# atv_sheild1.net
KiCad netlist of a schematic drawn in EAGLE
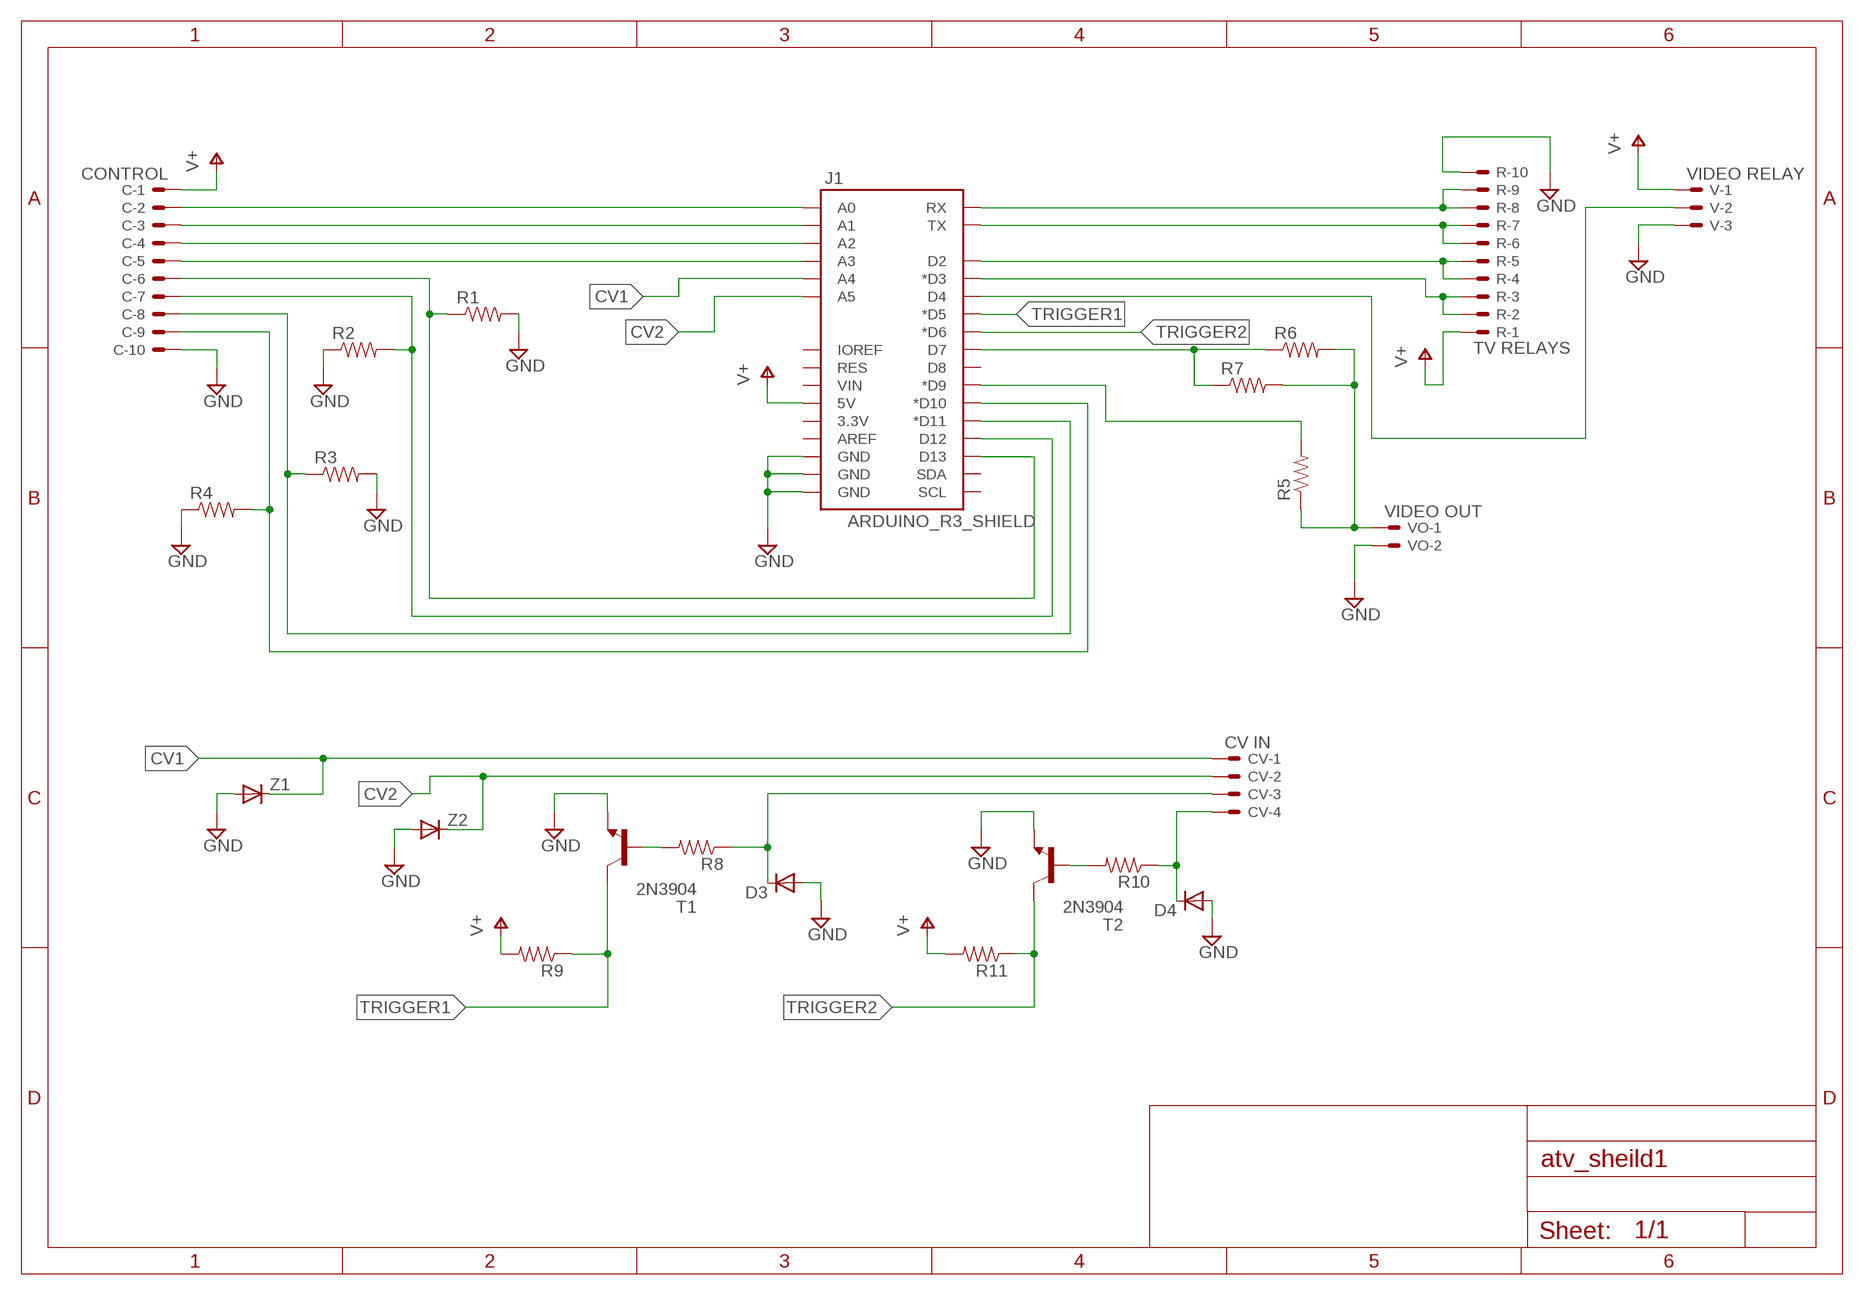
[diagram p0: schematic, sheet 1]

(export (version "E")
  (design (tool "Eeschema 10.0.6"))
  (components
    (comp (ref "C")
      (value "CONTROL")
      (footprint "eagle-import:22-23-2101")
      (fields (field (name "MF") "MOLEX") (field (name "MPN") "22-23-2101"))
      (libsource (lib "eagle-import") (part "22-23-2101"))
    )
    (comp (ref "CV")
      (value "CV IN")
      (footprint "eagle-import:22-23-2041")
      (fields (field (name "MF") "MOLEX") (field (name "MPN") "22-23-2041"))
      (libsource (lib "eagle-import") (part "22-23-2041"))
    )
    (comp (ref "D3")
      (value "SMALL_DIODEDO35-7")
      (footprint "eagle-import:DO35-7")
      (libsource (lib "eagle-import") (part "SMALL_DIODEDO35-7"))
    )
    (comp (ref "D4")
      (value "SMALL_DIODEDO35-7")
      (footprint "eagle-import:DO35-7")
      (libsource (lib "eagle-import") (part "SMALL_DIODEDO35-7"))
    )
    (comp (ref "J1")
      (value "ARDUINO_R3_SHIELD")
      (footprint "eagle-import:UNO_R3_SHIELD")
      (libsource (lib "eagle-import") (part "ARDUINO_R3_SHIELD"))
    )
    (comp (ref "R")
      (value "TV RELAYS")
      (footprint "eagle-import:22-23-2101")
      (fields (field (name "MF") "MOLEX") (field (name "MPN") "22-23-2101"))
      (libsource (lib "eagle-import") (part "22-23-2101"))
    )
    (comp (ref "R1")
      (value "RESISTORPTH-1/4W")
      (footprint "eagle-import:AXIAL-0.4")
      (libsource (lib "eagle-import") (part "RESISTORPTH-1/4W"))
    )
    (comp (ref "R2")
      (value "RESISTORPTH-1/4W")
      (footprint "eagle-import:AXIAL-0.4")
      (libsource (lib "eagle-import") (part "RESISTORPTH-1/4W"))
    )
    (comp (ref "R3")
      (value "RESISTORPTH-1/4W")
      (footprint "eagle-import:AXIAL-0.4")
      (libsource (lib "eagle-import") (part "RESISTORPTH-1/4W"))
    )
    (comp (ref "R4")
      (value "RESISTORPTH-1/4W")
      (footprint "eagle-import:AXIAL-0.4")
      (libsource (lib "eagle-import") (part "RESISTORPTH-1/4W"))
    )
    (comp (ref "R5")
      (value "RESISTORPTH-1/4W")
      (footprint "eagle-import:AXIAL-0.4")
      (libsource (lib "eagle-import") (part "RESISTORPTH-1/4W"))
    )
    (comp (ref "R6")
      (value "RESISTORPTH-1/4W")
      (footprint "eagle-import:AXIAL-0.4")
      (libsource (lib "eagle-import") (part "RESISTORPTH-1/4W"))
    )
    (comp (ref "R7")
      (value "RESISTORPTH-1/4W")
      (footprint "eagle-import:AXIAL-0.4")
      (libsource (lib "eagle-import") (part "RESISTORPTH-1/4W"))
    )
    (comp (ref "R8")
      (value "RESISTORPTH-1/4W")
      (footprint "eagle-import:AXIAL-0.4")
      (libsource (lib "eagle-import") (part "RESISTORPTH-1/4W"))
    )
    (comp (ref "R9")
      (value "RESISTORPTH-1/4W")
      (footprint "eagle-import:AXIAL-0.4")
      (libsource (lib "eagle-import") (part "RESISTORPTH-1/4W"))
    )
    (comp (ref "R10")
      (value "RESISTORPTH-1/4W")
      (footprint "eagle-import:AXIAL-0.4")
      (libsource (lib "eagle-import") (part "RESISTORPTH-1/4W"))
    )
    (comp (ref "R11")
      (value "RESISTORPTH-1/4W")
      (footprint "eagle-import:AXIAL-0.4")
      (libsource (lib "eagle-import") (part "RESISTORPTH-1/4W"))
    )
    (comp (ref "T1")
      (value "2N3904")
      (footprint "eagle-import:TO92")
      (libsource (lib "eagle-import") (part "2N3904"))
    )
    (comp (ref "T2")
      (value "2N3904")
      (footprint "eagle-import:TO92")
      (libsource (lib "eagle-import") (part "2N3904"))
    )
    (comp (ref "V")
      (value "VIDEO RELAY")
      (footprint "eagle-import:22-23-2031")
      (fields (field (name "MF") "MOLEX") (field (name "MPN") "22-23-2031"))
      (libsource (lib "eagle-import") (part "22-23-2031"))
    )
    (comp (ref "VO")
      (value "VIDEO OUT")
      (footprint "eagle-import:22-23-2021")
      (fields (field (name "MF") "MOLEX") (field (name "MPN") "22-23-2021"))
      (libsource (lib "eagle-import") (part "22-23-2021"))
    )
    (comp (ref "Z1")
      (value "SMALL_DIODEDO35-7")
      (footprint "eagle-import:DO35-7")
      (libsource (lib "eagle-import") (part "SMALL_DIODEDO35-7"))
    )
    (comp (ref "Z2")
      (value "SMALL_DIODEDO35-7")
      (footprint "eagle-import:DO35-7")
      (libsource (lib "eagle-import") (part "SMALL_DIODEDO35-7"))
    )
  )
  (nets
    (net (code "1") (name "CV1") (class "Default")
      (node (ref "CV") (pin "1") (pinfunction "S_1") (pintype "passive"))
      (node (ref "J1") (pin "A4") (pinfunction "A4_A4") (pintype "bidirectional"))
      (node (ref "Z1") (pin "C") (pinfunction "C_C") (pintype "passive"))
    )
    (net (code "2") (name "CV2") (class "Default")
      (node (ref "CV") (pin "2") (pinfunction "S_2") (pintype "passive"))
      (node (ref "J1") (pin "A5") (pinfunction "A5_A5") (pintype "bidirectional"))
      (node (ref "Z2") (pin "C") (pinfunction "C_C") (pintype "passive"))
    )
    (net (code "3") (name "GND") (class "Default")
      (node (ref "C") (pin "10") (pinfunction "S_10") (pintype "passive"))
      (node (ref "D3") (pin "A") (pinfunction "A_A") (pintype "passive"))
      (node (ref "D4") (pin "A") (pinfunction "A_A") (pintype "passive"))
      (node (ref "J1") (pin "GND@0") (pinfunction "GND_GND@0") (pintype "bidirectional"))
      (node (ref "J1") (pin "GND@1") (pinfunction "GND_GND@1") (pintype "bidirectional"))
      (node (ref "J1") (pin "GND@2") (pinfunction "GND_GND@2") (pintype "bidirectional"))
      (node (ref "R") (pin "10") (pinfunction "S_10") (pintype "passive"))
      (node (ref "R1") (pin "P$2") (pinfunction "2_P$2") (pintype "passive"))
      (node (ref "R2") (pin "P$1") (pinfunction "1_P$1") (pintype "passive"))
      (node (ref "R3") (pin "P$2") (pinfunction "2_P$2") (pintype "passive"))
      (node (ref "R4") (pin "P$1") (pinfunction "1_P$1") (pintype "passive"))
      (node (ref "T1") (pin "3") (pinfunction "E_3") (pintype "passive"))
      (node (ref "T2") (pin "3") (pinfunction "E_3") (pintype "passive"))
      (node (ref "V") (pin "3") (pinfunction "S_3") (pintype "passive"))
      (node (ref "VO") (pin "2") (pinfunction "S_2") (pintype "passive"))
      (node (ref "Z1") (pin "A") (pinfunction "A_A") (pintype "passive"))
      (node (ref "Z2") (pin "A") (pinfunction "A_A") (pintype "passive"))
    )
    (net (code "4") (name "Net-(CC-S)") (class "Default")
      (node (ref "C") (pin "2") (pinfunction "S_2") (pintype "passive"))
      (node (ref "J1") (pin "A0") (pinfunction "A0_A0") (pintype "bidirectional"))
    )
    (net (code "5") (name "Net-(CD-S)") (class "Default")
      (node (ref "C") (pin "3") (pinfunction "S_3") (pintype "passive"))
      (node (ref "J1") (pin "A1") (pinfunction "A1_A1") (pintype "bidirectional"))
    )
    (net (code "6") (name "Net-(CE-S)") (class "Default")
      (node (ref "C") (pin "4") (pinfunction "S_4") (pintype "passive"))
      (node (ref "J1") (pin "A2") (pinfunction "A2_A2") (pintype "bidirectional"))
    )
    (net (code "7") (name "Net-(CF-S)") (class "Default")
      (node (ref "C") (pin "5") (pinfunction "S_5") (pintype "passive"))
      (node (ref "J1") (pin "A3") (pinfunction "A3_A3") (pintype "bidirectional"))
    )
    (net (code "8") (name "Net-(CG-S)") (class "Default")
      (node (ref "C") (pin "6") (pinfunction "S_6") (pintype "passive"))
      (node (ref "J1") (pin "D13") (pinfunction "D13_D13") (pintype "bidirectional"))
      (node (ref "R1") (pin "P$1") (pinfunction "1_P$1") (pintype "passive"))
    )
    (net (code "9") (name "Net-(CH-S)") (class "Default")
      (node (ref "C") (pin "7") (pinfunction "S_7") (pintype "passive"))
      (node (ref "J1") (pin "D12") (pinfunction "D12_D12") (pintype "bidirectional"))
      (node (ref "R2") (pin "P$2") (pinfunction "2_P$2") (pintype "passive"))
    )
    (net (code "10") (name "Net-(CI-S)") (class "Default")
      (node (ref "C") (pin "8") (pinfunction "S_8") (pintype "passive"))
      (node (ref "J1") (pin "D11") (pinfunction "*D11_D11") (pintype "bidirectional"))
      (node (ref "R3") (pin "P$1") (pinfunction "1_P$1") (pintype "passive"))
    )
    (net (code "11") (name "Net-(CJ-S)") (class "Default")
      (node (ref "C") (pin "9") (pinfunction "S_9") (pintype "passive"))
      (node (ref "J1") (pin "D10") (pinfunction "*D10_D10") (pintype "bidirectional"))
      (node (ref "R4") (pin "P$2") (pinfunction "2_P$2") (pintype "passive"))
    )
    (net (code "12") (name "Net-(CVC-S)") (class "Default")
      (node (ref "CV") (pin "3") (pinfunction "S_3") (pintype "passive"))
      (node (ref "D3") (pin "C") (pinfunction "C_C") (pintype "passive"))
      (node (ref "R8") (pin "P$1") (pinfunction "1_P$1") (pintype "passive"))
    )
    (net (code "13") (name "Net-(CVD-S)") (class "Default")
      (node (ref "CV") (pin "4") (pinfunction "S_4") (pintype "passive"))
      (node (ref "D4") (pin "C") (pinfunction "C_C") (pintype "passive"))
      (node (ref "R10") (pin "P$1") (pinfunction "1_P$1") (pintype "passive"))
    )
    (net (code "14") (name "Net-(J1-*D3)") (class "Default")
      (node (ref "J1") (pin "D3") (pinfunction "*D3_D3") (pintype "bidirectional"))
      (node (ref "R") (pin "2") (pinfunction "S_2") (pintype "passive"))
      (node (ref "R") (pin "3") (pinfunction "S_3") (pintype "passive"))
    )
    (net (code "15") (name "Net-(J1-*D9)") (class "Default")
      (node (ref "J1") (pin "D9") (pinfunction "*D9_D9") (pintype "bidirectional"))
      (node (ref "R5") (pin "P$2") (pinfunction "2_P$2") (pintype "passive"))
    )
    (net (code "16") (name "Net-(R5-1)") (class "Default")
      (node (ref "R5") (pin "P$1") (pinfunction "1_P$1") (pintype "passive"))
      (node (ref "R6") (pin "P$2") (pinfunction "2_P$2") (pintype "passive"))
      (node (ref "R7") (pin "P$2") (pinfunction "2_P$2") (pintype "passive"))
      (node (ref "VO") (pin "1") (pinfunction "S_1") (pintype "passive"))
    )
    (net (code "17") (name "Net-(R6-1)") (class "Default")
      (node (ref "J1") (pin "D7") (pinfunction "D7_D7") (pintype "bidirectional"))
      (node (ref "R6") (pin "P$1") (pinfunction "1_P$1") (pintype "passive"))
      (node (ref "R7") (pin "P$1") (pinfunction "1_P$1") (pintype "passive"))
    )
    (net (code "18") (name "Net-(R8-2)") (class "Default")
      (node (ref "R8") (pin "P$2") (pinfunction "2_P$2") (pintype "passive"))
      (node (ref "T1") (pin "2") (pinfunction "B_2") (pintype "passive"))
    )
    (net (code "19") (name "Net-(R10-2)") (class "Default")
      (node (ref "R10") (pin "P$2") (pinfunction "2_P$2") (pintype "passive"))
      (node (ref "T2") (pin "2") (pinfunction "B_2") (pintype "passive"))
    )
    (net (code "20") (name "Net-(RE-S)") (class "Default")
      (node (ref "J1") (pin "D2") (pinfunction "D2_D2") (pintype "bidirectional"))
      (node (ref "R") (pin "4") (pinfunction "S_4") (pintype "passive"))
      (node (ref "R") (pin "5") (pinfunction "S_5") (pintype "passive"))
    )
    (net (code "21") (name "Net-(RG-S)") (class "Default")
      (node (ref "J1") (pin "TX") (pinfunction "TX_TX") (pintype "bidirectional"))
      (node (ref "R") (pin "6") (pinfunction "S_6") (pintype "passive"))
      (node (ref "R") (pin "7") (pinfunction "S_7") (pintype "passive"))
    )
    (net (code "22") (name "Net-(RI-S)") (class "Default")
      (node (ref "J1") (pin "RX") (pinfunction "RX_RX") (pintype "bidirectional"))
      (node (ref "R") (pin "8") (pinfunction "S_8") (pintype "passive"))
      (node (ref "R") (pin "9") (pinfunction "S_9") (pintype "passive"))
    )
    (net (code "23") (name "Net-(VB-S)") (class "Default")
      (node (ref "J1") (pin "D4") (pinfunction "D4_D4") (pintype "bidirectional"))
      (node (ref "V") (pin "2") (pinfunction "S_2") (pintype "passive"))
    )
    (net (code "24") (name "TRIGGER1") (class "Default")
      (node (ref "J1") (pin "D5") (pinfunction "*D5_D5") (pintype "bidirectional"))
      (node (ref "R9") (pin "P$1") (pinfunction "1_P$1") (pintype "passive"))
      (node (ref "T1") (pin "1") (pinfunction "C_1") (pintype "passive"))
    )
    (net (code "25") (name "TRIGGER2") (class "Default")
      (node (ref "J1") (pin "D6") (pinfunction "*D6_D6") (pintype "bidirectional"))
      (node (ref "R11") (pin "P$1") (pinfunction "1_P$1") (pintype "passive"))
      (node (ref "T2") (pin "1") (pinfunction "C_1") (pintype "passive"))
    )
    (net (code "26") (name "V+") (class "Default")
      (node (ref "C") (pin "1") (pinfunction "S_1") (pintype "passive"))
      (node (ref "J1") (pin "5V") (pinfunction "5V_5V") (pintype "bidirectional"))
      (node (ref "R") (pin "1") (pinfunction "S_1") (pintype "passive"))
      (node (ref "R11") (pin "P$2") (pinfunction "2_P$2") (pintype "passive"))
      (node (ref "R9") (pin "P$2") (pinfunction "2_P$2") (pintype "passive"))
      (node (ref "V") (pin "1") (pinfunction "S_1") (pintype "passive"))
    )
    (net (code "27") (name "unconnected-(J1-Pad3.3V)") (class "Default")
      (node (ref "J1") (pin "3.3V") (pinfunction "3.3V_3.3V") (pintype "bidirectional"))
    )
    (net (code "28") (name "unconnected-(J1-PadAREF)") (class "Default")
      (node (ref "J1") (pin "AREF") (pinfunction "AREF_AREF") (pintype "bidirectional"))
    )
    (net (code "29") (name "unconnected-(J1-PadD8)") (class "Default")
      (node (ref "J1") (pin "D8") (pinfunction "D8_D8") (pintype "bidirectional"))
    )
    (net (code "30") (name "unconnected-(J1-PadIOREF)") (class "Default")
      (node (ref "J1") (pin "IOREF") (pinfunction "IOREF_IOREF") (pintype "bidirectional"))
    )
    (net (code "31") (name "unconnected-(J1-PadRES)") (class "Default")
      (node (ref "J1") (pin "RES") (pinfunction "RES_RES") (pintype "bidirectional"))
    )
    (net (code "32") (name "unconnected-(J1-PadSCL)") (class "Default")
      (node (ref "J1") (pin "SCL") (pinfunction "SCL_SCL") (pintype "bidirectional"))
    )
    (net (code "33") (name "unconnected-(J1-PadSDA)") (class "Default")
      (node (ref "J1") (pin "SDA") (pinfunction "SDA_SDA") (pintype "bidirectional"))
    )
    (net (code "34") (name "unconnected-(J1-PadVIN)") (class "Default")
      (node (ref "J1") (pin "VIN") (pinfunction "VIN_VIN") (pintype "bidirectional"))
    )
  )
)
